# Output.net
KiCad netlist of a schematic drawn in Altium Designer
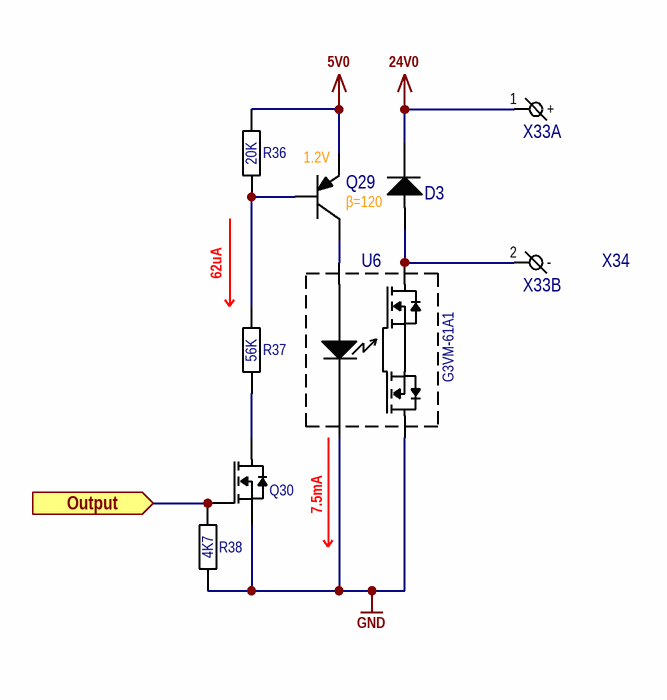
[diagram p0: Output.SchDoc]

(export (version "E")
  (design (tool "Eeschema 10.0.6"))
  (components
    (comp (ref "D3")
      (value "D")
      (footprint "SOT23-3")
      (description "RF DIODE SCHOTTKY 70V SOT23-3")
      (fields (field (name "13. CREATED DATE/NAME") "AUG 2018 / Hören"))
      (libsource (lib "tom") (part "HSMS-2800-TR1G"))
    )
    (comp (ref "Q29")
      (value "Q")
      (footprint "SOT23-3")
      (description "TRANS PNP 25V 1.5A SOT-23")
      (fields
        (field (name "02. DISTRIBUTOR PART NUMBER") "MMSS8550-L-TPMSDKR-ND")
        (field (name "07. MANUFACTURER  PART NUMBER") "MMSS8550-L-TP")
        (field (name "HFE") "β=120")
        (field (name "13. CREATED DATE/NAME") "AUG 2018 / Hören")
      )
      (libsource (lib "tom") (part "MMSS8550-L-TP"))
    )
    (comp (ref "Q30")
      (value "Q")
      (footprint "SOT23-3")
      (description "MOSFET N-CH 25V 680MA SOT-23")
      (fields
        (field (name "02. DISTRIBUTOR PART NUMBER") "FDV303NDKR-ND")
        (field (name "07. MANUFACTURER  PART NUMBER") "FDV303N")
        (field (name "13. CREATED DATE/NAME") "AUG 2018 / Hören")
      )
      (libsource (lib "SCT8-Board1") (part "FDV303N"))
    )
    (comp (ref "R36")
      (value "20K")
      (footprint "R0201 Reflow")
      (description "RES SMD 20K OHM 5% 1/10W 0603")
      (fields
        (field (name "TOLERANCE") "±5%")
        (field (name "02. DISTRIBUTOR PART NUMBER") "311-20KGRDKR-ND")
        (field (name "13. CREATED DATE/NAME") "AUG2018/Hören")
      )
      (libsource (lib "chickenfood") (part "R"))
    )
    (comp (ref "R37")
      (value "56K")
      (footprint "R0603 Reflow")
      (description "RES SMD 56K OHM 5% 1/10W 0603")
      (fields
        (field (name "TOLERANCE") "±5%")
        (field (name "02. DISTRIBUTOR PART NUMBER") "P56KGDKR-ND")
        (field (name "13. CREATED DATE/NAME") "AUG2018/Hören")
      )
      (libsource (lib "chickenfood") (part "R"))
    )
    (comp (ref "R38")
      (value "4K7")
      (footprint "R0402 Reflow")
      (description "Resistor")
      (fields
        (field (name "TOLERANCE") "±1%")
        (field (name "Comment") "R")
        (field (name "13. CREATED DATE/NAME") "AUG2018/Hören")
      )
      (libsource (lib "chickenfood") (part "R"))
    )
    (comp (ref "U6")
      (value "U")
      (footprint "4DIP")
      (description "SSR RELAY SPST-NO 500MA 0-60V")
      (fields
        (field (name "02. DISTRIBUTOR PART NUMBER") "Z2100-ND")
        (field (name "07. MANUFACTURER  PART NUMBER") "G3VM-61A1")
        (field (name "NICNAME") "G3VM-61A1")
        (field (name "13. CREATED DATE/NAME") "AUG 2018 / Hören")
      )
      (libsource (lib "tom") (part "G3VM-61A1"))
    )
    (comp (ref "X33")
      (value "X")
      (footprint "691322310002")
      (description "TERM BLOCK HDR 2POS 90DEG 3.81MM")
      (fields
        (field (name "02. DISTRIBUTOR PART NUMBER") "732-2088-ND")
        (field (name "07. MANUFACTURER  PART NUMBER") "691322310002")
        (field (name "13. CREATED DATE/NAME") "??? / Hören")
      )
      (libsource (lib "") (part "691322310002_1"))
    )
    (comp (ref "X34")
      (value "X")
      (footprint "691361300002")
      (description "TERM BLOCK PLUG 2POS STR 3.81MM")
      (fields (field (name "13. CREATED DATE/NAME") "??? / Hören"))
      (libsource (lib "Connectors") (part "691361300002"))
    )
  )
  (nets
    (net (code "1") (name "/Output") (class "Default")
      (node (ref "Q30") (pin "1") (pinfunction "G_1") (pintype "passive"))
      (node (ref "R38") (pin "2") (pinfunction "2_2") (pintype "passive"))
    )
    (net (code "2") (name "5V0") (class "Default")
      (node (ref "Q29") (pin "2") (pinfunction "E_2") (pintype "passive"))
      (node (ref "R36") (pin "2") (pinfunction "2_2") (pintype "passive"))
    )
    (net (code "3") (name "24V0") (class "Default")
      (node (ref "D3") (pin "3") (pinfunction "C_3") (pintype "passive"))
      (node (ref "X33") (pin "1") (pinfunction "+_1") (pintype "passive"))
    )
    (net (code "4") (name "GND") (class "Default")
      (node (ref "Q30") (pin "2") (pinfunction "S_2") (pintype "passive"))
      (node (ref "R38") (pin "1") (pinfunction "1_1") (pintype "passive"))
      (node (ref "U6") (pin "2") (pinfunction "C_2") (pintype "passive"))
      (node (ref "U6") (pin "3") (pinfunction "D_3") (pintype "passive"))
    )
    (net (code "5") (name "Net-(D3-A)") (class "Default")
      (node (ref "D3") (pin "1") (pinfunction "A_1") (pintype "passive"))
      (node (ref "U6") (pin "4") (pinfunction "D_4") (pintype "passive"))
      (node (ref "X33") (pin "2") (pinfunction "-_2") (pintype "passive"))
    )
    (net (code "6") (name "Net-(Q29-B)") (class "Default")
      (node (ref "Q29") (pin "1") (pinfunction "B_1") (pintype "passive"))
      (node (ref "R36") (pin "1") (pinfunction "1_1") (pintype "passive"))
      (node (ref "R37") (pin "2") (pinfunction "2_2") (pintype "passive"))
    )
    (net (code "7") (name "Net-(Q29-C)") (class "Default")
      (node (ref "Q29") (pin "3") (pinfunction "C_3") (pintype "passive"))
      (node (ref "U6") (pin "1") (pinfunction "A_1") (pintype "passive"))
    )
    (net (code "8") (name "Net-(Q30-D)") (class "Default")
      (node (ref "Q30") (pin "3") (pinfunction "D_3") (pintype "passive"))
      (node (ref "R37") (pin "1") (pinfunction "1_1") (pintype "passive"))
    )
  )
)
